# Compressor_Remote_Cntrl_Board.net
KiCad netlist of a schematic drawn in EAGLE
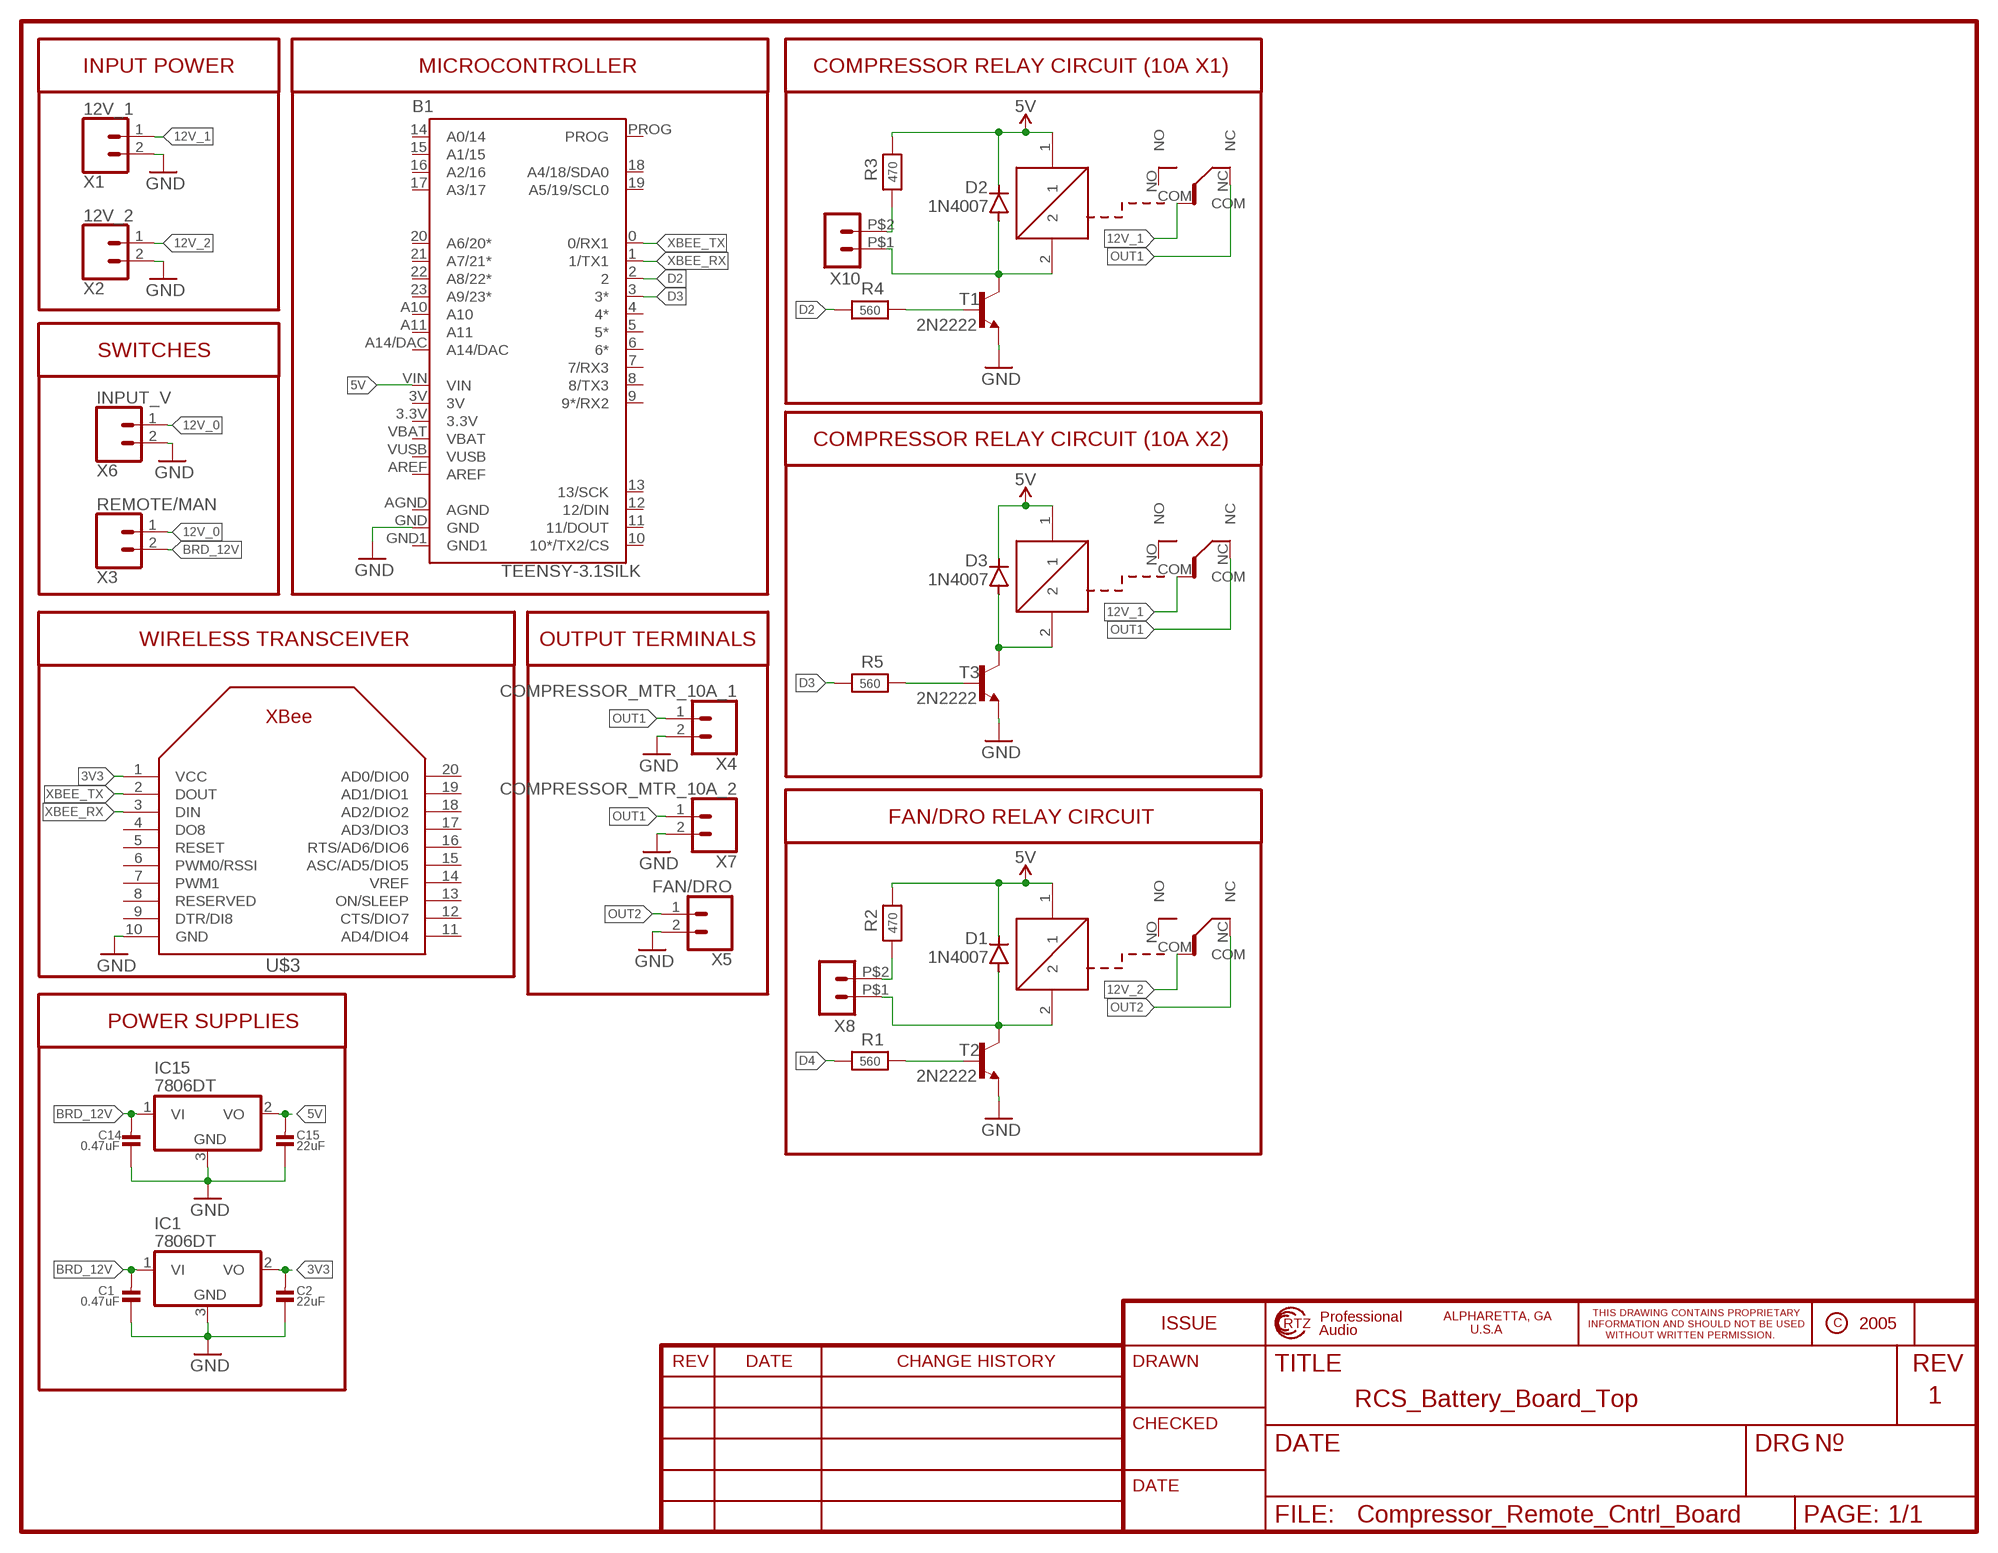
[diagram p0: schematic, sheet 1]

(export (version "E")
  (design (tool "Eeschema 10.0.6"))
  (components
    (comp (ref "B1")
      (value "TEENSY-3.1SILK")
      (footprint "eagle-import:TEENSY-3.1")
      (libsource (lib "eagle-import") (part "TEENSY-3.1SILK"))
    )
    (comp (ref "C1")
      (value "0.47uF")
      (footprint "eagle-import:0603")
      (libsource (lib "eagle-import") (part "CAP_CERAMIC0603"))
    )
    (comp (ref "C2")
      (value "22uF")
      (footprint "eagle-import:0603")
      (libsource (lib "eagle-import") (part "CAP_CERAMIC0603"))
    )
    (comp (ref "C14")
      (value "0.47uF")
      (footprint "eagle-import:0603")
      (libsource (lib "eagle-import") (part "CAP_CERAMIC0603"))
    )
    (comp (ref "C15")
      (value "22uF")
      (footprint "eagle-import:0603")
      (libsource (lib "eagle-import") (part "CAP_CERAMIC0603"))
    )
    (comp (ref "D1")
      (value "1N4007")
      (footprint "eagle-import:DO-41")
      (fields
        (field (name "DIGIKEY_PART_NUMBER") "1N4007MSCT-ND")
        (field (name "MANUFACTURER") "Micro Commercial Co")
        (field (name "CREATED_BY") "PCBLayout.com")
      )
      (libsource (lib "eagle-import") (part "1N4007"))
    )
    (comp (ref "D2")
      (value "1N4007")
      (footprint "eagle-import:DO-41")
      (fields
        (field (name "DIGIKEY_PART_NUMBER") "1N4007MSCT-ND")
        (field (name "MANUFACTURER") "Micro Commercial Co")
        (field (name "CREATED_BY") "PCBLayout.com")
      )
      (libsource (lib "eagle-import") (part "1N4007"))
    )
    (comp (ref "D3")
      (value "1N4007")
      (footprint "eagle-import:DO-41")
      (fields
        (field (name "DIGIKEY_PART_NUMBER") "1N4007MSCT-ND")
        (field (name "MANUFACTURER") "Micro Commercial Co")
        (field (name "CREATED_BY") "PCBLayout.com")
      )
      (libsource (lib "eagle-import") (part "1N4007"))
    )
    (comp (ref "IC1")
      (value "7806DT")
      (footprint "eagle-import:TO252")
      (libsource (lib "eagle-import") (part "78DT06"))
    )
    (comp (ref "IC15")
      (value "7806DT")
      (footprint "eagle-import:TO252")
      (libsource (lib "eagle-import") (part "78DT06"))
    )
    (comp (ref "R1")
      (value "560")
      (footprint "eagle-import:0805")
      (libsource (lib "eagle-import") (part "RESISTOR0805"))
    )
    (comp (ref "R2")
      (value "470")
      (footprint "eagle-import:0805")
      (libsource (lib "eagle-import") (part "RESISTOR0805"))
    )
    (comp (ref "R3")
      (value "470")
      (footprint "eagle-import:0805")
      (libsource (lib "eagle-import") (part "RESISTOR0805"))
    )
    (comp (ref "R4")
      (value "560")
      (footprint "eagle-import:0805")
      (libsource (lib "eagle-import") (part "RESISTOR0805"))
    )
    (comp (ref "R5")
      (value "560")
      (footprint "eagle-import:0805")
      (libsource (lib "eagle-import") (part "RESISTOR0805"))
    )
    (comp (ref "T1")
      (value "2N2222")
      (footprint "eagle-import:TO92-EBC-OVAL")
      (libsource (lib "eagle-import") (part "2N2222"))
    )
    (comp (ref "T2")
      (value "2N2222")
      (footprint "eagle-import:TO92-EBC-OVAL")
      (libsource (lib "eagle-import") (part "2N2222"))
    )
    (comp (ref "T3")
      (value "2N2222")
      (footprint "eagle-import:TO92-EBC-OVAL")
      (libsource (lib "eagle-import") (part "2N2222"))
    )
    (comp (ref "U$1")
      (value "RW-SH")
      (footprint "eagle-import:RW-SH")
      (libsource (lib "eagle-import") (part "RW-SH"))
    )
    (comp (ref "U$2")
      (value "RW-SH")
      (footprint "eagle-import:RW-SH")
      (libsource (lib "eagle-import") (part "RW-SH"))
    )
    (comp (ref "U$3")
      (value "XBEE")
      (footprint "eagle-import:XBEE")
      (libsource (lib "eagle-import") (part "XBEE"))
    )
    (comp (ref "U$4")
      (value "RW-SH")
      (footprint "eagle-import:RW-SH")
      (libsource (lib "eagle-import") (part "RW-SH"))
    )
    (comp (ref "X1")
      (value "12V_1")
      (footprint "eagle-import:SCREWTERMINAL-5MM-2")
      (libsource (lib "eagle-import") (part "CONN_025MM"))
    )
    (comp (ref "X2")
      (value "12V_2")
      (footprint "eagle-import:SCREWTERMINAL-5MM-2")
      (libsource (lib "eagle-import") (part "CONN_025MM"))
    )
    (comp (ref "X3")
      (value "REMOTE/MAN")
      (footprint "eagle-import:SCREWTERMINAL-5MM-2")
      (libsource (lib "eagle-import") (part "CONN_025MM"))
    )
    (comp (ref "X4")
      (value "COMPRESSOR_MTR_10A_1")
      (footprint "eagle-import:SCREWTERMINAL-5MM-2")
      (libsource (lib "eagle-import") (part "CONN_025MM"))
    )
    (comp (ref "X5")
      (value "FAN/DRO")
      (footprint "eagle-import:SCREWTERMINAL-5MM-2")
      (libsource (lib "eagle-import") (part "CONN_025MM"))
    )
    (comp (ref "X6")
      (value "INPUT_V")
      (footprint "eagle-import:SCREWTERMINAL-5MM-2")
      (libsource (lib "eagle-import") (part "CONN_025MM"))
    )
    (comp (ref "X7")
      (value "COMPRESSOR_MTR_10A_2")
      (footprint "eagle-import:SCREWTERMINAL-5MM-2")
      (libsource (lib "eagle-import") (part "CONN_025MM"))
    )
    (comp (ref "X8")
      (value "HEADER_POS2_43650-0215")
      (footprint "eagle-import:43650-0215")
      (libsource (lib "eagle-import") (part "HEADER_POS2_?43650-0215"))
    )
    (comp (ref "X10")
      (value "HEADER_POS2_43650-0215")
      (footprint "eagle-import:43650-0215")
      (libsource (lib "eagle-import") (part "HEADER_POS2_?43650-0215"))
    )
  )
  (nets
    (net (code "1") (name "/3.3V") (class "Default")
      (node (ref "B1") (pin "3.3V") (pinfunction "3.3V_3.3V") (pintype "power_in"))
    )
    (net (code "2") (name "/3V") (class "Default")
      (node (ref "B1") (pin "3V") (pinfunction "3V_3V") (pintype "power_in"))
    )
    (net (code "3") (name "/AGND") (class "Default")
      (node (ref "B1") (pin "AGND") (pinfunction "AGND_AGND") (pintype "power_in"))
    )
    (net (code "4") (name "/GND1") (class "Default")
      (node (ref "B1") (pin "GND1") (pinfunction "GND1_GND1") (pintype "power_in"))
    )
    (net (code "5") (name "/VBAT") (class "Default")
      (node (ref "B1") (pin "VBAT") (pinfunction "VBAT_VBAT") (pintype "power_in"))
    )
    (net (code "6") (name "/VUSB") (class "Default")
      (node (ref "B1") (pin "VUSB") (pinfunction "VUSB_VUSB") (pintype "power_in"))
    )
    (net (code "7") (name "3V3") (class "Default")
      (node (ref "C2") (pin "2") (pinfunction "P$2_2") (pintype "passive"))
      (node (ref "IC1") (pin "2") (pinfunction "VO_2") (pintype "passive"))
      (node (ref "U$3") (pin "1") (pinfunction "VCC_1") (pintype "power_in"))
    )
    (net (code "8") (name "5V") (class "Default")
      (node (ref "B1") (pin "VIN") (pinfunction "VIN_VIN") (pintype "power_in"))
      (node (ref "C15") (pin "2") (pinfunction "P$2_2") (pintype "passive"))
      (node (ref "D1") (pin "C") (pinfunction "C_C") (pintype "passive"))
      (node (ref "D2") (pin "C") (pinfunction "C_C") (pintype "passive"))
      (node (ref "D3") (pin "C") (pinfunction "C_C") (pintype "passive"))
      (node (ref "IC15") (pin "2") (pinfunction "VO_2") (pintype "passive"))
      (node (ref "R2") (pin "2") (pinfunction "2_2") (pintype "passive"))
      (node (ref "R3") (pin "2") (pinfunction "2_2") (pintype "passive"))
      (node (ref "U$1") (pin "1") (pinfunction "1_1") (pintype "bidirectional"))
      (node (ref "U$2") (pin "1") (pinfunction "1_1") (pintype "bidirectional"))
      (node (ref "U$4") (pin "1") (pinfunction "1_1") (pintype "bidirectional"))
    )
    (net (code "9") (name "12V_0") (class "Default")
      (node (ref "X3") (pin "1") (pinfunction "1_1") (pintype "passive"))
      (node (ref "X6") (pin "1") (pinfunction "1_1") (pintype "passive"))
    )
    (net (code "10") (name "12V_1") (class "Default")
      (node (ref "U$2") (pin "COM") (pinfunction "COM_COM") (pintype "bidirectional"))
      (node (ref "U$4") (pin "COM") (pinfunction "COM_COM") (pintype "bidirectional"))
      (node (ref "X1") (pin "1") (pinfunction "1_1") (pintype "passive"))
    )
    (net (code "11") (name "12V_2") (class "Default")
      (node (ref "U$1") (pin "COM") (pinfunction "COM_COM") (pintype "bidirectional"))
      (node (ref "X2") (pin "1") (pinfunction "1_1") (pintype "passive"))
    )
    (net (code "12") (name "BRD_12V") (class "Default")
      (node (ref "C1") (pin "2") (pinfunction "P$2_2") (pintype "passive"))
      (node (ref "C14") (pin "2") (pinfunction "P$2_2") (pintype "passive"))
      (node (ref "IC1") (pin "1") (pinfunction "VI_1") (pintype "input"))
      (node (ref "IC15") (pin "1") (pinfunction "VI_1") (pintype "input"))
      (node (ref "X3") (pin "2") (pinfunction "2_2") (pintype "passive"))
    )
    (net (code "13") (name "D2") (class "Default")
      (node (ref "B1") (pin "2") (pinfunction "2_2") (pintype "bidirectional"))
      (node (ref "R4") (pin "1") (pinfunction "1_1") (pintype "passive"))
    )
    (net (code "14") (name "D3") (class "Default")
      (node (ref "B1") (pin "3") (pinfunction "3*_3") (pintype "bidirectional"))
      (node (ref "R5") (pin "1") (pinfunction "1_1") (pintype "passive"))
    )
    (net (code "15") (name "D4") (class "Default")
      (node (ref "R1") (pin "1") (pinfunction "1_1") (pintype "passive"))
    )
    (net (code "16") (name "GND") (class "Default")
      (node (ref "B1") (pin "GND") (pinfunction "GND_GND") (pintype "power_in"))
      (node (ref "C1") (pin "1") (pinfunction "P$1_1") (pintype "passive"))
      (node (ref "C14") (pin "1") (pinfunction "P$1_1") (pintype "passive"))
      (node (ref "C15") (pin "1") (pinfunction "P$1_1") (pintype "passive"))
      (node (ref "C2") (pin "1") (pinfunction "P$1_1") (pintype "passive"))
      (node (ref "IC1") (pin "3") (pinfunction "GND_3") (pintype "passive"))
      (node (ref "IC15") (pin "3") (pinfunction "GND_3") (pintype "passive"))
      (node (ref "T1") (pin "E") (pinfunction "E_E") (pintype "passive"))
      (node (ref "T2") (pin "E") (pinfunction "E_E") (pintype "passive"))
      (node (ref "T3") (pin "E") (pinfunction "E_E") (pintype "passive"))
      (node (ref "U$3") (pin "10") (pinfunction "GND_10") (pintype "power_in"))
      (node (ref "X1") (pin "2") (pinfunction "2_2") (pintype "passive"))
      (node (ref "X2") (pin "2") (pinfunction "2_2") (pintype "passive"))
      (node (ref "X4") (pin "2") (pinfunction "2_2") (pintype "passive"))
      (node (ref "X5") (pin "2") (pinfunction "2_2") (pintype "passive"))
      (node (ref "X6") (pin "2") (pinfunction "2_2") (pintype "passive"))
      (node (ref "X7") (pin "2") (pinfunction "2_2") (pintype "passive"))
    )
    (net (code "17") (name "Net-(D3-PadA)") (class "Default")
      (node (ref "D3") (pin "A") (pinfunction "A_A") (pintype "passive"))
      (node (ref "T3") (pin "C") (pinfunction "C_C") (pintype "passive"))
      (node (ref "U$4") (pin "2") (pinfunction "2_2") (pintype "bidirectional"))
    )
    (net (code "18") (name "Net-(R1-Pad2)") (class "Default")
      (node (ref "R1") (pin "2") (pinfunction "2_2") (pintype "passive"))
      (node (ref "T2") (pin "B") (pinfunction "B_B") (pintype "passive"))
    )
    (net (code "19") (name "Net-(R4-Pad2)") (class "Default")
      (node (ref "R4") (pin "2") (pinfunction "2_2") (pintype "passive"))
      (node (ref "T1") (pin "B") (pinfunction "B_B") (pintype "passive"))
    )
    (net (code "20") (name "Net-(R5-Pad2)") (class "Default")
      (node (ref "R5") (pin "2") (pinfunction "2_2") (pintype "passive"))
      (node (ref "T3") (pin "B") (pinfunction "B_B") (pintype "passive"))
    )
    (net (code "21") (name "Net-(X8-1)") (class "Default")
      (node (ref "D1") (pin "A") (pinfunction "A_A") (pintype "passive"))
      (node (ref "T2") (pin "C") (pinfunction "C_C") (pintype "passive"))
      (node (ref "U$1") (pin "2") (pinfunction "2_2") (pintype "bidirectional"))
      (node (ref "X8") (pin "P$1") (pinfunction "1_P$1") (pintype "passive"))
    )
    (net (code "22") (name "Net-(X8-2)") (class "Default")
      (node (ref "R2") (pin "1") (pinfunction "1_1") (pintype "passive"))
      (node (ref "X8") (pin "P$2") (pinfunction "2_P$2") (pintype "passive"))
    )
    (net (code "23") (name "Net-(X10-1)") (class "Default")
      (node (ref "D2") (pin "A") (pinfunction "A_A") (pintype "passive"))
      (node (ref "T1") (pin "C") (pinfunction "C_C") (pintype "passive"))
      (node (ref "U$2") (pin "2") (pinfunction "2_2") (pintype "bidirectional"))
      (node (ref "X10") (pin "P$1") (pinfunction "1_P$1") (pintype "passive"))
    )
    (net (code "24") (name "Net-(X10-2)") (class "Default")
      (node (ref "R3") (pin "1") (pinfunction "1_1") (pintype "passive"))
      (node (ref "X10") (pin "P$2") (pinfunction "2_P$2") (pintype "passive"))
    )
    (net (code "25") (name "OUT1") (class "Default")
      (node (ref "U$2") (pin "NC") (pinfunction "NC_NC") (pintype "bidirectional"))
      (node (ref "U$4") (pin "NC") (pinfunction "NC_NC") (pintype "bidirectional"))
      (node (ref "X4") (pin "1") (pinfunction "1_1") (pintype "passive"))
      (node (ref "X7") (pin "1") (pinfunction "1_1") (pintype "passive"))
    )
    (net (code "26") (name "OUT2") (class "Default")
      (node (ref "U$1") (pin "NC") (pinfunction "NC_NC") (pintype "bidirectional"))
      (node (ref "X5") (pin "1") (pinfunction "1_1") (pintype "passive"))
    )
    (net (code "27") (name "XBEE_RX") (class "Default")
      (node (ref "B1") (pin "1") (pinfunction "1/TX1_1") (pintype "bidirectional"))
      (node (ref "U$3") (pin "3") (pinfunction "DIN_3") (pintype "input"))
    )
    (net (code "28") (name "XBEE_TX") (class "Default")
      (node (ref "B1") (pin "0") (pinfunction "0/RX1_0") (pintype "bidirectional"))
      (node (ref "U$3") (pin "2") (pinfunction "DOUT_2") (pintype "output"))
    )
    (net (code "29") (name "unconnected-(B1-4*-Pad4)") (class "Default")
      (node (ref "B1") (pin "4") (pinfunction "4*_4") (pintype "bidirectional"))
    )
    (net (code "30") (name "unconnected-(B1-5*-Pad5)") (class "Default")
      (node (ref "B1") (pin "5") (pinfunction "5*_5") (pintype "bidirectional"))
    )
    (net (code "31") (name "unconnected-(B1-6*-Pad6)") (class "Default")
      (node (ref "B1") (pin "6") (pinfunction "6*_6") (pintype "bidirectional"))
    )
    (net (code "32") (name "unconnected-(B1-7{slash}RX3-Pad7)") (class "Default")
      (node (ref "B1") (pin "7") (pinfunction "7/RX3_7") (pintype "bidirectional"))
    )
    (net (code "33") (name "unconnected-(B1-8{slash}TX3-Pad8)") (class "Default")
      (node (ref "B1") (pin "8") (pinfunction "8/TX3_8") (pintype "bidirectional"))
    )
    (net (code "34") (name "unconnected-(B1-9*{slash}RX2-Pad9)") (class "Default")
      (node (ref "B1") (pin "9") (pinfunction "9*/RX2_9") (pintype "bidirectional"))
    )
    (net (code "35") (name "unconnected-(B1-10*{slash}TX2{slash}CS-Pad10)") (class "Default")
      (node (ref "B1") (pin "10") (pinfunction "10*/TX2/CS_10") (pintype "bidirectional"))
    )
    (net (code "36") (name "unconnected-(B1-11{slash}DOUT-Pad11)") (class "Default")
      (node (ref "B1") (pin "11") (pinfunction "11/DOUT_11") (pintype "bidirectional"))
    )
    (net (code "37") (name "unconnected-(B1-12{slash}DIN-Pad12)") (class "Default")
      (node (ref "B1") (pin "12") (pinfunction "12/DIN_12") (pintype "bidirectional"))
    )
    (net (code "38") (name "unconnected-(B1-13{slash}SCK-Pad13)") (class "Default")
      (node (ref "B1") (pin "13") (pinfunction "13/SCK_13") (pintype "bidirectional"))
    )
    (net (code "39") (name "unconnected-(B1-A0{slash}14-Pad14)") (class "Default")
      (node (ref "B1") (pin "14") (pinfunction "A0/14_14") (pintype "bidirectional"))
    )
    (net (code "40") (name "unconnected-(B1-A1{slash}15-Pad15)") (class "Default")
      (node (ref "B1") (pin "15") (pinfunction "A1/15_15") (pintype "bidirectional"))
    )
    (net (code "41") (name "unconnected-(B1-A2{slash}16-Pad16)") (class "Default")
      (node (ref "B1") (pin "16") (pinfunction "A2/16_16") (pintype "bidirectional"))
    )
    (net (code "42") (name "unconnected-(B1-A3{slash}17-Pad17)") (class "Default")
      (node (ref "B1") (pin "17") (pinfunction "A3/17_17") (pintype "bidirectional"))
    )
    (net (code "43") (name "unconnected-(B1-A4{slash}18{slash}SDA0-Pad18)") (class "Default")
      (node (ref "B1") (pin "18") (pinfunction "A4/18/SDA0_18") (pintype "bidirectional"))
    )
    (net (code "44") (name "unconnected-(B1-A5{slash}19{slash}SCL0-Pad19)") (class "Default")
      (node (ref "B1") (pin "19") (pinfunction "A5/19/SCL0_19") (pintype "bidirectional"))
    )
    (net (code "45") (name "unconnected-(B1-A6{slash}20*-Pad20)") (class "Default")
      (node (ref "B1") (pin "20") (pinfunction "A6/20*_20") (pintype "bidirectional"))
    )
    (net (code "46") (name "unconnected-(B1-A7{slash}21*-Pad21)") (class "Default")
      (node (ref "B1") (pin "21") (pinfunction "A7/21*_21") (pintype "bidirectional"))
    )
    (net (code "47") (name "unconnected-(B1-A8{slash}22*-Pad22)") (class "Default")
      (node (ref "B1") (pin "22") (pinfunction "A8/22*_22") (pintype "bidirectional"))
    )
    (net (code "48") (name "unconnected-(B1-A9{slash}23*-Pad23)") (class "Default")
      (node (ref "B1") (pin "23") (pinfunction "A9/23*_23") (pintype "bidirectional"))
    )
    (net (code "49") (name "unconnected-(B1-PadA10)") (class "Default")
      (node (ref "B1") (pin "A10") (pinfunction "A10_A10") (pintype "bidirectional"))
    )
    (net (code "50") (name "unconnected-(B1-PadA11)") (class "Default")
      (node (ref "B1") (pin "A11") (pinfunction "A11_A11") (pintype "bidirectional"))
    )
    (net (code "51") (name "unconnected-(B1-PadA14{slash}DAC)") (class "Default")
      (node (ref "B1") (pin "A14/DAC") (pinfunction "A14/DAC_A14/DAC") (pintype "bidirectional"))
    )
    (net (code "52") (name "unconnected-(B1-PadAREF)") (class "Default")
      (node (ref "B1") (pin "AREF") (pinfunction "AREF_AREF") (pintype "bidirectional"))
    )
    (net (code "53") (name "unconnected-(B1-PadPROG)") (class "Default")
      (node (ref "B1") (pin "PROG") (pinfunction "PROG_PROG") (pintype "bidirectional"))
    )
    (net (code "54") (name "unconnected-(U$1-PadNO)") (class "Default")
      (node (ref "U$1") (pin "NO") (pinfunction "NO_NO") (pintype "bidirectional"))
    )
    (net (code "55") (name "unconnected-(U$2-PadNO)") (class "Default")
      (node (ref "U$2") (pin "NO") (pinfunction "NO_NO") (pintype "bidirectional"))
    )
    (net (code "56") (name "unconnected-(U$3-AD0{slash}DIO0-Pad20)") (class "Default")
      (node (ref "U$3") (pin "20") (pinfunction "AD0/DIO0_20") (pintype "bidirectional"))
    )
    (net (code "57") (name "unconnected-(U$3-AD1{slash}DIO1-Pad19)") (class "Default")
      (node (ref "U$3") (pin "19") (pinfunction "AD1/DIO1_19") (pintype "bidirectional"))
    )
    (net (code "58") (name "unconnected-(U$3-AD2{slash}DIO2-Pad18)") (class "Default")
      (node (ref "U$3") (pin "18") (pinfunction "AD2/DIO2_18") (pintype "bidirectional"))
    )
    (net (code "59") (name "unconnected-(U$3-AD3{slash}DIO3-Pad17)") (class "Default")
      (node (ref "U$3") (pin "17") (pinfunction "AD3/DIO3_17") (pintype "bidirectional"))
    )
    (net (code "60") (name "unconnected-(U$3-AD4{slash}DIO4-Pad11)") (class "Default")
      (node (ref "U$3") (pin "11") (pinfunction "AD4/DIO4_11") (pintype "bidirectional"))
    )
    (net (code "61") (name "unconnected-(U$3-ASC{slash}AD5{slash}DIO5-Pad15)") (class "Default")
      (node (ref "U$3") (pin "15") (pinfunction "ASC/AD5/DIO5_15") (pintype "bidirectional"))
    )
    (net (code "62") (name "unconnected-(U$3-CTS{slash}DIO7-Pad12)") (class "Default")
      (node (ref "U$3") (pin "12") (pinfunction "CTS/DIO7_12") (pintype "bidirectional"))
    )
    (net (code "63") (name "unconnected-(U$3-DO8-Pad4)") (class "Default")
      (node (ref "U$3") (pin "4") (pinfunction "DO8_4") (pintype "output"))
    )
    (net (code "64") (name "unconnected-(U$3-DTR{slash}DI8-Pad9)") (class "Default")
      (node (ref "U$3") (pin "9") (pinfunction "DTR/DI8_9") (pintype "input"))
    )
    (net (code "65") (name "unconnected-(U$3-ON{slash}SLEEP-Pad13)") (class "Default")
      (node (ref "U$3") (pin "13") (pinfunction "ON/SLEEP_13") (pintype "output"))
    )
    (net (code "66") (name "unconnected-(U$3-PWM0{slash}RSSI-Pad6)") (class "Default")
      (node (ref "U$3") (pin "6") (pinfunction "PWM0/RSSI_6") (pintype "output"))
    )
    (net (code "67") (name "unconnected-(U$3-PWM1-Pad7)") (class "Default")
      (node (ref "U$3") (pin "7") (pinfunction "PWM1_7") (pintype "output"))
    )
    (net (code "68") (name "unconnected-(U$3-RESERVED-Pad8)") (class "Default")
      (node (ref "U$3") (pin "8") (pinfunction "RESERVED_8") (pintype "no_connect"))
    )
    (net (code "69") (name "unconnected-(U$3-RESET-Pad5)") (class "Default")
      (node (ref "U$3") (pin "5") (pinfunction "RESET_5") (pintype "input"))
    )
    (net (code "70") (name "unconnected-(U$3-RTS{slash}AD6{slash}DIO6-Pad16)") (class "Default")
      (node (ref "U$3") (pin "16") (pinfunction "RTS/AD6/DIO6_16") (pintype "bidirectional"))
    )
    (net (code "71") (name "unconnected-(U$3-VREF-Pad14)") (class "Default")
      (node (ref "U$3") (pin "14") (pinfunction "VREF_14") (pintype "input"))
    )
    (net (code "72") (name "unconnected-(U$4-PadNO)") (class "Default")
      (node (ref "U$4") (pin "NO") (pinfunction "NO_NO") (pintype "bidirectional"))
    )
  )
)
